# bloom.net
KiCad netlist of a schematic drawn in EAGLE
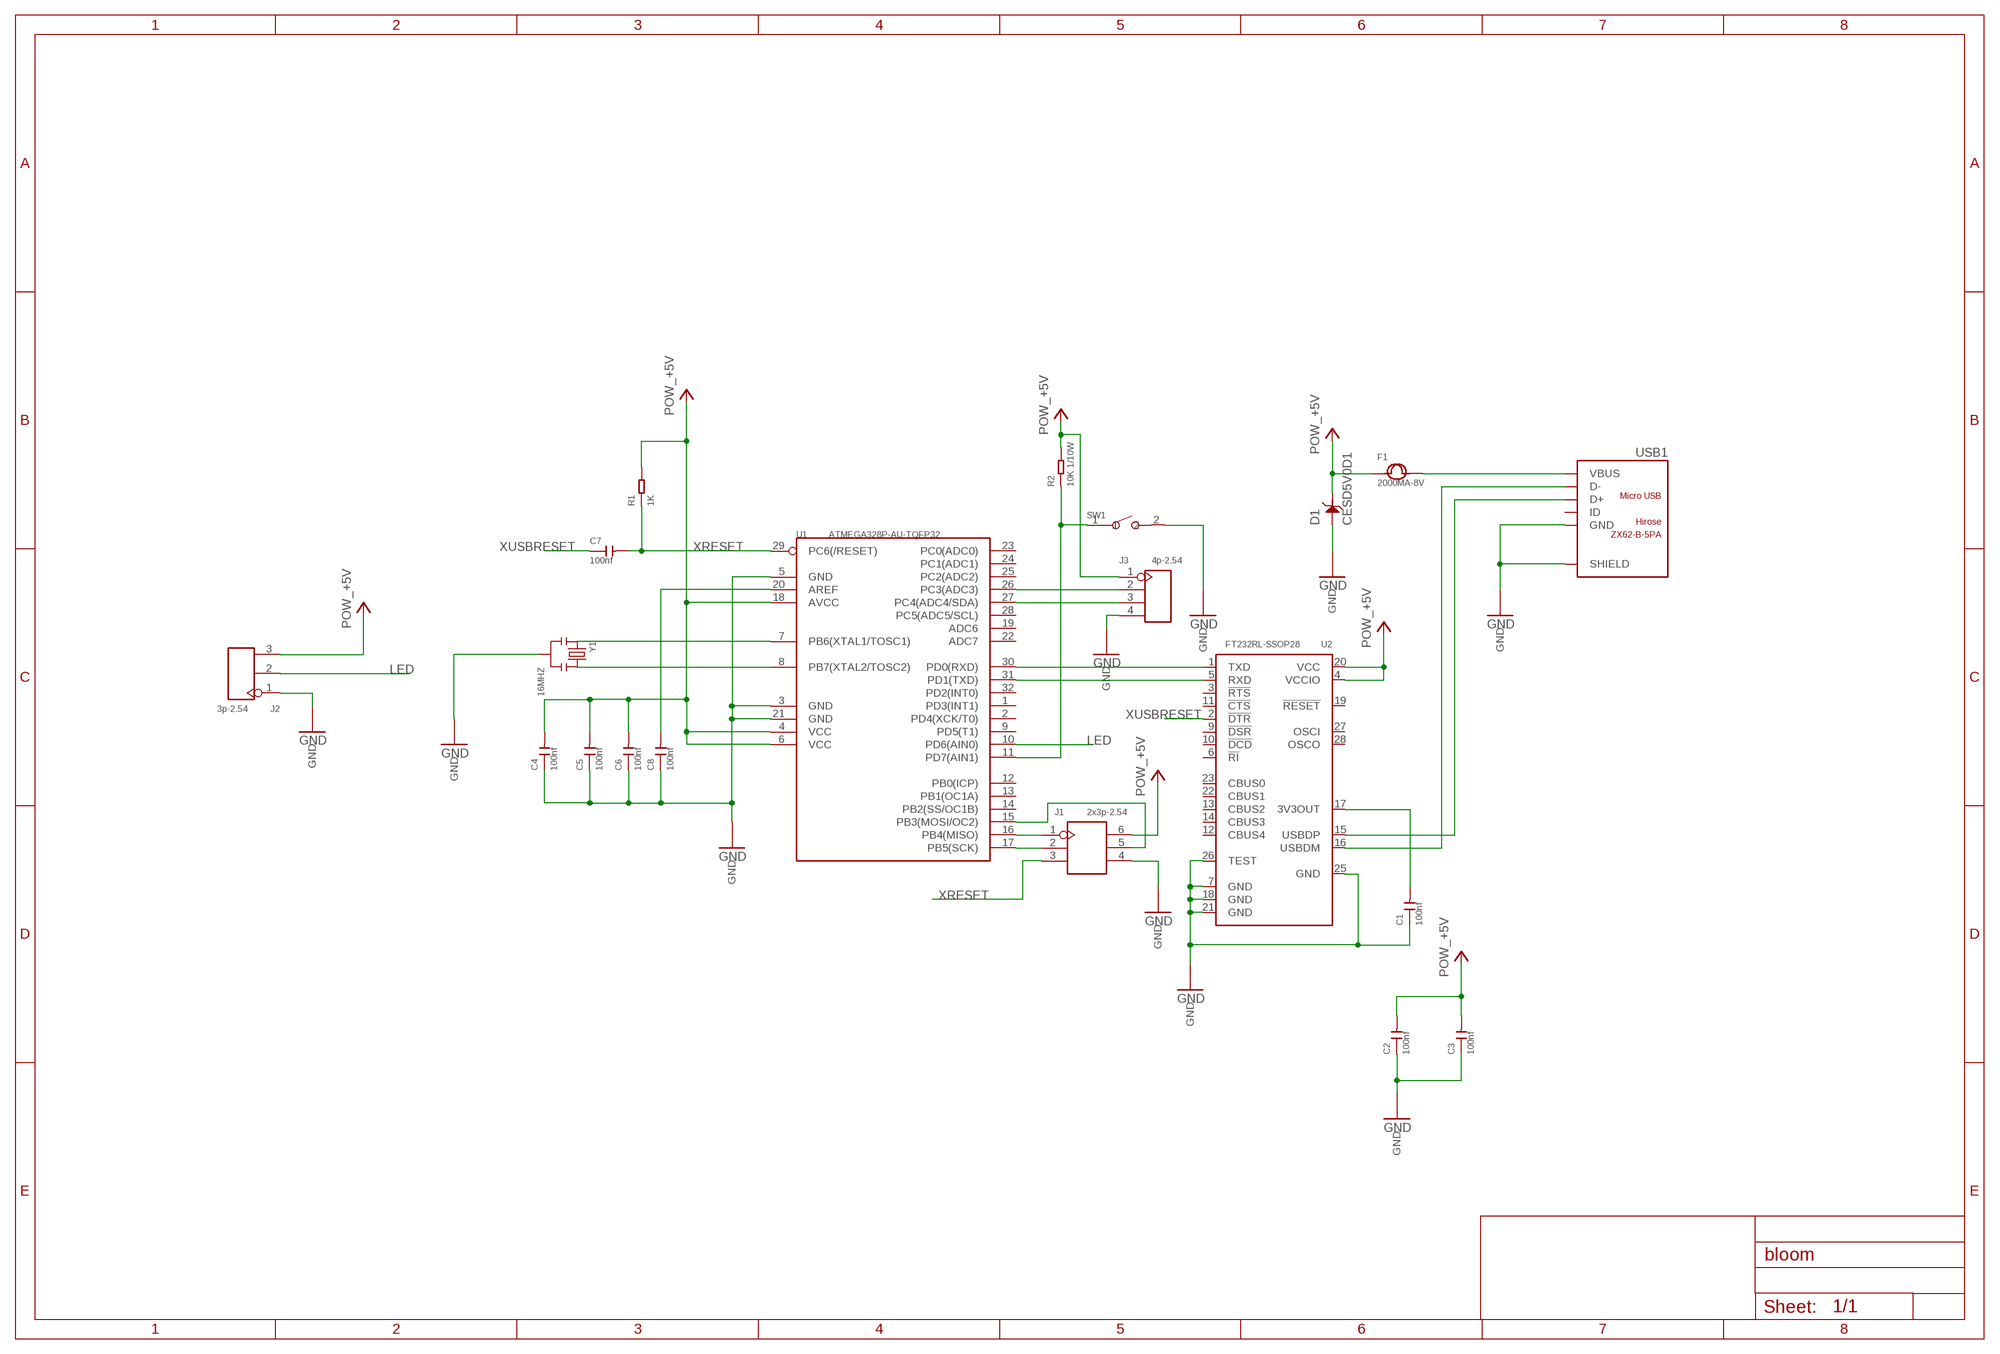
[diagram p0: schematic, sheet 1]

(export (version "E")
  (design (tool "Eeschema 10.0.6"))
  (components
    (comp (ref "C1")
      (value "100nf")
      (footprint "eagle-import:C0402")
      (fields (field (name "MPN") "CC0402KRX7R8BB104"))
      (libsource (lib "eagle-import") (part "CERAMIC-100NF-25V-10%-X7R(0402)"))
    )
    (comp (ref "C2")
      (value "100nf")
      (footprint "eagle-import:C0402")
      (fields (field (name "MPN") "CC0402KRX7R8BB104"))
      (libsource (lib "eagle-import") (part "CERAMIC-100NF-25V-10%-X7R(0402)"))
    )
    (comp (ref "C3")
      (value "100nf")
      (footprint "eagle-import:C0402")
      (fields (field (name "MPN") "CC0402KRX7R8BB104"))
      (libsource (lib "eagle-import") (part "CERAMIC-100NF-25V-10%-X7R(0402)"))
    )
    (comp (ref "C4")
      (value "100nf")
      (footprint "eagle-import:C0402")
      (fields (field (name "MPN") "CC0402KRX7R8BB104"))
      (libsource (lib "eagle-import") (part "CERAMIC-100NF-25V-10%-X7R(0402)"))
    )
    (comp (ref "C5")
      (value "100nf")
      (footprint "eagle-import:C0402")
      (fields (field (name "MPN") "CC0402KRX7R8BB104"))
      (libsource (lib "eagle-import") (part "CERAMIC-100NF-25V-10%-X7R(0402)"))
    )
    (comp (ref "C6")
      (value "100nf")
      (footprint "eagle-import:C0402")
      (fields (field (name "MPN") "CC0402KRX7R8BB104"))
      (libsource (lib "eagle-import") (part "CERAMIC-100NF-25V-10%-X7R(0402)"))
    )
    (comp (ref "C7")
      (value "100nf")
      (footprint "eagle-import:C0402")
      (fields (field (name "MPN") "CC0402KRX7R8BB104"))
      (libsource (lib "eagle-import") (part "CERAMIC-100NF-25V-10%-X7R(0402)"))
    )
    (comp (ref "C8")
      (value "100nf")
      (footprint "eagle-import:C0402")
      (fields (field (name "MPN") "CC0402KRX7R8BB104"))
      (libsource (lib "eagle-import") (part "CERAMIC-100NF-25V-10%-X7R(0402)"))
    )
    (comp (ref "D1")
      (value "CESD5V0D1")
      (footprint "eagle-import:SOD-123")
      (libsource (lib "eagle-import") (part "SMD-DIODE-ESD-6.2V-250MW(SOD-123)"))
    )
    (comp (ref "F1")
      (value "2000MA-8V")
      (footprint "eagle-import:F1210")
      (fields (field (name "MPN") "SMD1210R075SF"))
      (libsource (lib "eagle-import") (part "SMD-PPTC-750MA-6V(1210)"))
    )
    (comp (ref "J1")
      (value "2x3p-2.54")
      (footprint "eagle-import:H2X3-2.54")
      (fields (field (name "MPN") "F185-1203A1BSYA1"))
      (libsource (lib "eagle-import") (part "DIP-BLACK-FEMALE-HEADER-VERT(2X3P-2.54)"))
    )
    (comp (ref "J2")
      (value "3p-2.54")
      (footprint "eagle-import:H3-2.54")
      (fields (field (name "MPN") "F185-1103A0BSYA1"))
      (libsource (lib "eagle-import") (part "DIP-BLACK-FEMALE-HEADER-VERT(3P-2.54)"))
    )
    (comp (ref "J3")
      (value "4p-2.54")
      (footprint "eagle-import:H4-2.54")
      (fields (field (name "MPN") "F185-1104A1BSYA1"))
      (libsource (lib "eagle-import") (part "DIP-BLACK-FEMALE-HEADER-VERT(4P-2.54)"))
    )
    (comp (ref "R1")
      (value "1K")
      (footprint "eagle-import:R0603")
      (fields (field (name "MPN") "RC0603FR-071KL"))
      (libsource (lib "eagle-import") (part "SMD-RES-1K-1%-1/10W(0603)"))
    )
    (comp (ref "R2")
      (value "10K 1/10W")
      (footprint "eagle-import:R0603")
      (fields (field (name "MPN") "RC0603JR-0710KL"))
      (libsource (lib "eagle-import") (part "SMD-RES-10K-5%-1/10W(0603)"))
    )
    (comp (ref "SW1")
      (value "SMD-BUTTON(2P-3.0X2.5X1.2+0.4MM)-B3U-1000P-2P-SMD")
      (footprint "eagle-import:SW2-2.6-3.0X2.5X1.2+0.4MM")
      (libsource (lib "eagle-import") (part "SMD-BUTTON(2P-3.0X2.5X1.2+0.4MM)-B3U-1000P-2P-SMD"))
    )
    (comp (ref "U1")
      (value "ATMEGA328P-AU-TQFP32")
      (footprint "eagle-import:TQFP32-0.8-7X7MM")
      (fields (field (name "MPN") "ATMEGA328P-AU"))
      (libsource (lib "eagle-import") (part "MCU-ATMEGA328P-AU(TQFP32)"))
    )
    (comp (ref "U2")
      (value "FT232RL-SSOP28")
      (footprint "eagle-import:SSOP28-0.65-10.2X5.2MM")
      (fields (field (name "MPN") "FT232RL"))
      (libsource (lib "eagle-import") (part "INTERFACE-FT232RL(SSOP28)"))
    )
    (comp (ref "USB1")
      (value "ZX62-B-5PA")
      (footprint "eagle-import:MICRO-USB5+6P-SMD-0.65-AB")
      (libsource (lib "eagle-import") (part "MICRO-USB-SMD(ZX62-B-5PA)"))
    )
    (comp (ref "Y1")
      (value "16MHZ")
      (footprint "eagle-import:X3-SMD-3.6X1.3X0.8MM")
      (fields (field (name "MPN") "CSTCE16M0V53-R0"))
      (libsource (lib "eagle-import") (part "SMD-RESONATOR-16MHZ-15PF-0.5%-40R(3P-3.2X1.3MM)"))
    )
  )
  (nets
    (net (code "1") (name "/LED") (class "Default")
      (node (ref "J2") (pin "2") (pinfunction "P$2_2") (pintype "bidirectional"))
      (node (ref "U1") (pin "10") (pinfunction "PD6(AIN0)_10") (pintype "bidirectional"))
    )
    (net (code "2") (name "/XRESET") (class "Default")
      (node (ref "C7") (pin "2") (pinfunction "2_2") (pintype "passive"))
      (node (ref "J1") (pin "3") (pinfunction "3_3") (pintype "bidirectional"))
      (node (ref "R1") (pin "1") (pinfunction "1_1") (pintype "passive"))
      (node (ref "U1") (pin "29") (pinfunction "PC6(/RESET)_29") (pintype "bidirectional"))
    )
    (net (code "3") (name "/XUSBRESET") (class "Default")
      (node (ref "C7") (pin "1") (pinfunction "1_1") (pintype "passive"))
      (node (ref "U2") (pin "2") (pinfunction "~{DTR}_2") (pintype "input"))
    )
    (net (code "4") (name "GND") (class "Default")
      (node (ref "C1") (pin "1") (pinfunction "1_1") (pintype "passive"))
      (node (ref "C2") (pin "1") (pinfunction "1_1") (pintype "passive"))
      (node (ref "C3") (pin "1") (pinfunction "1_1") (pintype "passive"))
      (node (ref "C4") (pin "1") (pinfunction "1_1") (pintype "passive"))
      (node (ref "C5") (pin "1") (pinfunction "1_1") (pintype "passive"))
      (node (ref "C6") (pin "1") (pinfunction "1_1") (pintype "passive"))
      (node (ref "C8") (pin "1") (pinfunction "1_1") (pintype "passive"))
      (node (ref "D1") (pin "+") (pinfunction "1_+") (pintype "bidirectional"))
      (node (ref "J1") (pin "4") (pinfunction "4_4") (pintype "bidirectional"))
      (node (ref "J2") (pin "1") (pinfunction "P$1_1") (pintype "bidirectional"))
      (node (ref "J3") (pin "4") (pinfunction "P$4_4") (pintype "bidirectional"))
      (node (ref "SW1") (pin "2") (pinfunction "2_2") (pintype "bidirectional"))
      (node (ref "U1") (pin "21") (pinfunction "GND_21") (pintype "bidirectional"))
      (node (ref "U1") (pin "3") (pinfunction "GND_3") (pintype "bidirectional"))
      (node (ref "U1") (pin "5") (pinfunction "GND_5") (pintype "bidirectional"))
      (node (ref "U2") (pin "18") (pinfunction "GND_18") (pintype "input"))
      (node (ref "U2") (pin "21") (pinfunction "GND_21") (pintype "input"))
      (node (ref "U2") (pin "25") (pinfunction "GND_25") (pintype "input"))
      (node (ref "U2") (pin "26") (pinfunction "TEST_26") (pintype "input"))
      (node (ref "U2") (pin "7") (pinfunction "GND_7") (pintype "input"))
      (node (ref "USB1") (pin "5") (pinfunction "GND_5") (pintype "power_in"))
      (node (ref "USB1") (pin "P1") (pinfunction "SHIELD_P1") (pintype "power_in"))
      (node (ref "USB1") (pin "P2") (pinfunction "SHIELD_P2") (pintype "power_in"))
      (node (ref "USB1") (pin "P3") (pinfunction "SHIELD_P3") (pintype "power_in"))
      (node (ref "USB1") (pin "P4") (pinfunction "SHIELD_P4") (pintype "power_in"))
      (node (ref "USB1") (pin "P5") (pinfunction "SHIELD_P5") (pintype "power_in"))
      (node (ref "USB1") (pin "P6") (pinfunction "SHIELD_P6") (pintype "power_in"))
      (node (ref "Y1") (pin "2") (pinfunction "2_2") (pintype "passive"))
    )
    (net (code "5") (name "Net-(J3-P$2)") (class "Default")
      (node (ref "J3") (pin "2") (pinfunction "P$2_2") (pintype "bidirectional"))
      (node (ref "U1") (pin "26") (pinfunction "PC3(ADC3)_26") (pintype "bidirectional"))
    )
    (net (code "6") (name "Net-(J3-P$3)") (class "Default")
      (node (ref "J3") (pin "3") (pinfunction "P$3_3") (pintype "bidirectional"))
      (node (ref "U1") (pin "27") (pinfunction "PC4(ADC4/SDA)_27") (pintype "bidirectional"))
    )
    (net (code "7") (name "Net-(U1-AREF)") (class "Default")
      (node (ref "C8") (pin "2") (pinfunction "2_2") (pintype "passive"))
      (node (ref "U1") (pin "20") (pinfunction "AREF_20") (pintype "bidirectional"))
    )
    (net (code "8") (name "Net-(U1-PB3(MOSI{slash}OC2))") (class "Default")
      (node (ref "J1") (pin "5") (pinfunction "5_5") (pintype "bidirectional"))
      (node (ref "U1") (pin "15") (pinfunction "PB3(MOSI/OC2)_15") (pintype "bidirectional"))
    )
    (net (code "9") (name "Net-(U1-PB4(MISO))") (class "Default")
      (node (ref "J1") (pin "1") (pinfunction "1_1") (pintype "bidirectional"))
      (node (ref "U1") (pin "16") (pinfunction "PB4(MISO)_16") (pintype "bidirectional"))
    )
    (net (code "10") (name "Net-(U1-PB5(SCK))") (class "Default")
      (node (ref "J1") (pin "2") (pinfunction "2_2") (pintype "bidirectional"))
      (node (ref "U1") (pin "17") (pinfunction "PB5(SCK)_17") (pintype "bidirectional"))
    )
    (net (code "11") (name "Net-(U1-PB6(XTAL1{slash}TOSC1))") (class "Default")
      (node (ref "U1") (pin "7") (pinfunction "PB6(XTAL1/TOSC1)_7") (pintype "bidirectional"))
      (node (ref "Y1") (pin "1") (pinfunction "1_1") (pintype "passive"))
    )
    (net (code "12") (name "Net-(U1-PB7(XTAL2{slash}TOSC2))") (class "Default")
      (node (ref "U1") (pin "8") (pinfunction "PB7(XTAL2/TOSC2)_8") (pintype "bidirectional"))
      (node (ref "Y1") (pin "3") (pinfunction "3_3") (pintype "passive"))
    )
    (net (code "13") (name "Net-(U1-PD0(RXD))") (class "Default")
      (node (ref "U1") (pin "30") (pinfunction "PD0(RXD)_30") (pintype "bidirectional"))
      (node (ref "U2") (pin "1") (pinfunction "TXD_1") (pintype "input"))
    )
    (net (code "14") (name "Net-(U1-PD1(TXD))") (class "Default")
      (node (ref "U1") (pin "31") (pinfunction "PD1(TXD)_31") (pintype "bidirectional"))
      (node (ref "U2") (pin "5") (pinfunction "RXD_5") (pintype "input"))
    )
    (net (code "15") (name "Net-(U1-PD7(AIN1))") (class "Default")
      (node (ref "R2") (pin "1") (pinfunction "1_1") (pintype "passive"))
      (node (ref "SW1") (pin "1") (pinfunction "1_1") (pintype "bidirectional"))
      (node (ref "U1") (pin "11") (pinfunction "PD7(AIN1)_11") (pintype "bidirectional"))
    )
    (net (code "16") (name "Net-(U2-3V3OUT)") (class "Default")
      (node (ref "C1") (pin "2") (pinfunction "2_2") (pintype "passive"))
      (node (ref "U2") (pin "17") (pinfunction "3V3OUT_17") (pintype "input"))
    )
    (net (code "17") (name "Net-(U2-USBDM)") (class "Default")
      (node (ref "U2") (pin "16") (pinfunction "USBDM_16") (pintype "input"))
      (node (ref "USB1") (pin "2") (pinfunction "D-_2") (pintype "bidirectional"))
    )
    (net (code "18") (name "Net-(U2-USBDP)") (class "Default")
      (node (ref "U2") (pin "15") (pinfunction "USBDP_15") (pintype "input"))
      (node (ref "USB1") (pin "3") (pinfunction "D+_3") (pintype "bidirectional"))
    )
    (net (code "19") (name "Net-(USB1-VBUS)") (class "Default")
      (node (ref "F1") (pin "2") (pinfunction "2_2") (pintype "bidirectional"))
      (node (ref "USB1") (pin "1") (pinfunction "VBUS_1") (pintype "power_in"))
    )
    (net (code "20") (name "POW_+5V") (class "Default")
      (node (ref "C2") (pin "2") (pinfunction "2_2") (pintype "passive"))
      (node (ref "C3") (pin "2") (pinfunction "2_2") (pintype "passive"))
      (node (ref "C4") (pin "2") (pinfunction "2_2") (pintype "passive"))
      (node (ref "C5") (pin "2") (pinfunction "2_2") (pintype "passive"))
      (node (ref "C6") (pin "2") (pinfunction "2_2") (pintype "passive"))
      (node (ref "D1") (pin "-") (pinfunction "2_-") (pintype "bidirectional"))
      (node (ref "F1") (pin "1") (pinfunction "1_1") (pintype "bidirectional"))
      (node (ref "J1") (pin "6") (pinfunction "6_6") (pintype "bidirectional"))
      (node (ref "J2") (pin "3") (pinfunction "P$3_3") (pintype "bidirectional"))
      (node (ref "J3") (pin "1") (pinfunction "P$1_1") (pintype "bidirectional"))
      (node (ref "R1") (pin "2") (pinfunction "2_2") (pintype "passive"))
      (node (ref "R2") (pin "2") (pinfunction "2_2") (pintype "passive"))
      (node (ref "U1") (pin "18") (pinfunction "AVCC_18") (pintype "bidirectional"))
      (node (ref "U1") (pin "4") (pinfunction "VCC_4") (pintype "bidirectional"))
      (node (ref "U1") (pin "6") (pinfunction "VCC_6") (pintype "bidirectional"))
      (node (ref "U2") (pin "20") (pinfunction "VCC_20") (pintype "input"))
      (node (ref "U2") (pin "4") (pinfunction "VCCIO_4") (pintype "input"))
    )
    (net (code "21") (name "unconnected-(U1-ADC6-Pad19)") (class "Default")
      (node (ref "U1") (pin "19") (pinfunction "ADC6_19") (pintype "bidirectional"))
    )
    (net (code "22") (name "unconnected-(U1-ADC7-Pad22)") (class "Default")
      (node (ref "U1") (pin "22") (pinfunction "ADC7_22") (pintype "bidirectional"))
    )
    (net (code "23") (name "unconnected-(U1-PB0(ICP)-Pad12)") (class "Default")
      (node (ref "U1") (pin "12") (pinfunction "PB0(ICP)_12") (pintype "bidirectional"))
    )
    (net (code "24") (name "unconnected-(U1-PB1(OC1A)-Pad13)") (class "Default")
      (node (ref "U1") (pin "13") (pinfunction "PB1(OC1A)_13") (pintype "bidirectional"))
    )
    (net (code "25") (name "unconnected-(U1-PB2(SS{slash}OC1B)-Pad14)") (class "Default")
      (node (ref "U1") (pin "14") (pinfunction "PB2(SS/OC1B)_14") (pintype "bidirectional"))
    )
    (net (code "26") (name "unconnected-(U1-PC0(ADC0)-Pad23)") (class "Default")
      (node (ref "U1") (pin "23") (pinfunction "PC0(ADC0)_23") (pintype "bidirectional"))
    )
    (net (code "27") (name "unconnected-(U1-PC1(ADC1)-Pad24)") (class "Default")
      (node (ref "U1") (pin "24") (pinfunction "PC1(ADC1)_24") (pintype "bidirectional"))
    )
    (net (code "28") (name "unconnected-(U1-PC2(ADC2)-Pad25)") (class "Default")
      (node (ref "U1") (pin "25") (pinfunction "PC2(ADC2)_25") (pintype "bidirectional"))
    )
    (net (code "29") (name "unconnected-(U1-PC5(ADC5{slash}SCL)-Pad28)") (class "Default")
      (node (ref "U1") (pin "28") (pinfunction "PC5(ADC5/SCL)_28") (pintype "bidirectional"))
    )
    (net (code "30") (name "unconnected-(U1-PD2(INT0)-Pad32)") (class "Default")
      (node (ref "U1") (pin "32") (pinfunction "PD2(INT0)_32") (pintype "bidirectional"))
    )
    (net (code "31") (name "unconnected-(U1-PD3(INT1)-Pad1)") (class "Default")
      (node (ref "U1") (pin "1") (pinfunction "PD3(INT1)_1") (pintype "bidirectional"))
    )
    (net (code "32") (name "unconnected-(U1-PD4(XCK{slash}T0)-Pad2)") (class "Default")
      (node (ref "U1") (pin "2") (pinfunction "PD4(XCK/T0)_2") (pintype "bidirectional"))
    )
    (net (code "33") (name "unconnected-(U1-PD5(T1)-Pad9)") (class "Default")
      (node (ref "U1") (pin "9") (pinfunction "PD5(T1)_9") (pintype "bidirectional"))
    )
    (net (code "34") (name "unconnected-(U2-CBUS0-Pad23)") (class "Default")
      (node (ref "U2") (pin "23") (pinfunction "CBUS0_23") (pintype "input"))
    )
    (net (code "35") (name "unconnected-(U2-CBUS1-Pad22)") (class "Default")
      (node (ref "U2") (pin "22") (pinfunction "CBUS1_22") (pintype "input"))
    )
    (net (code "36") (name "unconnected-(U2-CBUS2-Pad13)") (class "Default")
      (node (ref "U2") (pin "13") (pinfunction "CBUS2_13") (pintype "input"))
    )
    (net (code "37") (name "unconnected-(U2-CBUS3-Pad14)") (class "Default")
      (node (ref "U2") (pin "14") (pinfunction "CBUS3_14") (pintype "input"))
    )
    (net (code "38") (name "unconnected-(U2-CBUS4-Pad12)") (class "Default")
      (node (ref "U2") (pin "12") (pinfunction "CBUS4_12") (pintype "input"))
    )
    (net (code "39") (name "unconnected-(U2-OSCI-Pad27)") (class "Default")
      (node (ref "U2") (pin "27") (pinfunction "OSCI_27") (pintype "input"))
    )
    (net (code "40") (name "unconnected-(U2-OSCO-Pad28)") (class "Default")
      (node (ref "U2") (pin "28") (pinfunction "OSCO_28") (pintype "input"))
    )
    (net (code "41") (name "unconnected-(U2-~{CTS}-Pad11)") (class "Default")
      (node (ref "U2") (pin "11") (pinfunction "~{CTS}_11") (pintype "input"))
    )
    (net (code "42") (name "unconnected-(U2-~{DCD}-Pad10)") (class "Default")
      (node (ref "U2") (pin "10") (pinfunction "~{DCD}_10") (pintype "input"))
    )
    (net (code "43") (name "unconnected-(U2-~{DSR}-Pad9)") (class "Default")
      (node (ref "U2") (pin "9") (pinfunction "~{DSR}_9") (pintype "input"))
    )
    (net (code "44") (name "unconnected-(U2-~{RESET}-Pad19)") (class "Default")
      (node (ref "U2") (pin "19") (pinfunction "~{RESET}_19") (pintype "input"))
    )
    (net (code "45") (name "unconnected-(U2-~{RI}-Pad6)") (class "Default")
      (node (ref "U2") (pin "6") (pinfunction "~{RI}_6") (pintype "input"))
    )
    (net (code "46") (name "unconnected-(U2-~{RTS}-Pad3)") (class "Default")
      (node (ref "U2") (pin "3") (pinfunction "~{RTS}_3") (pintype "input"))
    )
    (net (code "47") (name "unconnected-(USB1-ID-Pad4)") (class "Default")
      (node (ref "USB1") (pin "4") (pinfunction "ID_4") (pintype "bidirectional"))
    )
  )
)
